# ESP-Grow_OLED_Rev_A_1.net
KiCad netlist of a schematic drawn in Altium Designer
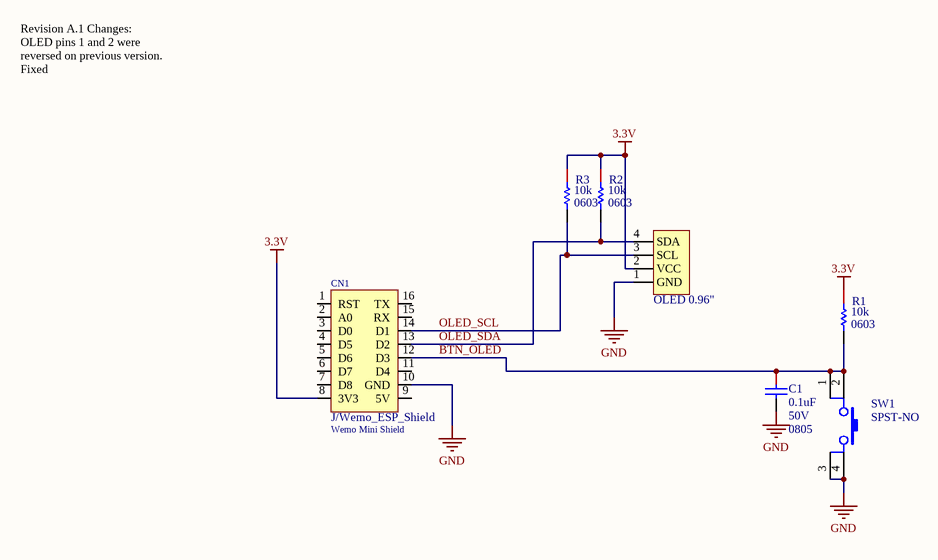
[diagram p0: ESP-Grow_OLED_Rev_A.1.SchDoc]

(export (version "E")
  (design (tool "Eeschema 10.0.6"))
  (components
    (comp (ref "C1")
      (value "0.1uF")
      (footprint "CAPC0805(2012)_L")
      (description "CAP CER 0.1UF 50V 10% X7R 0805")
      (fields
        (field (name "VOLTAGE (RATED)") "50V")
        (field (name "PACKAGE (IMPERIAL)") "0805")
        (field (name "TOLERANCE") "10%")
      )
      (libsource (lib "OLogic Nexus Vault") (part "=Capacitance"))
    )
    (comp (ref "CN1")
      (value "J/Wemo_ESP_Shield")
      (footprint "Wemos_d1_no3d")
      (description "Wemo Mini Shield for ESP-12")
      (fields (field (name "NAME") "Wemo Mini Shield"))
      (libsource (lib "Kyle_Lib_04-20-19") (part "J/Wemo_ESP_Shield"))
    )
    (comp (ref "J1")
      (value "OLED 0.96\"")
      (footprint "OLED_0.96_I2C")
      (description "SSD1306 I2C OLED 0.96\"")
      (libsource (lib "Kyle_Lib_04-20-19") (part "OLED_0.96_I2C"))
    )
    (comp (ref "R1")
      (value "10K")
      (footprint "RESC0603(1608)_M")
      (description "RES 10K OHM 1/10W 1% 0603 SMD")
      (fields
        (field (name "PACKAGE (IMPERIAL)") "0603")
        (field (name "RESISTANCE") "10k")
        (field (name "POWER") "100mW")
        (field (name "TOLERANCE") "1%")
      )
      (libsource (lib "OLogic Nexus Vault") (part "=Resistance"))
    )
    (comp (ref "R2")
      (value "10K")
      (footprint "RESC0603(1608)_M")
      (description "RES 10K OHM 1/10W 1% 0603 SMD")
      (fields
        (field (name "PACKAGE (IMPERIAL)") "0603")
        (field (name "RESISTANCE") "10k")
        (field (name "POWER") "100mW")
        (field (name "TOLERANCE") "1%")
      )
      (libsource (lib "OLogic Nexus Vault") (part "=Resistance"))
    )
    (comp (ref "R3")
      (value "10K")
      (footprint "RESC0603(1608)_M")
      (description "RES 10K OHM 1/10W 1% 0603 SMD")
      (fields
        (field (name "PACKAGE (IMPERIAL)") "0603")
        (field (name "RESISTANCE") "10k")
        (field (name "POWER") "100mW")
        (field (name "TOLERANCE") "1%")
      )
      (libsource (lib "OLogic Nexus Vault") (part "=Resistance"))
    )
    (comp (ref "SW1")
      (value "PTS645SM43SMTR92 LFS")
      (footprint "SW TACT Red 6mm x 6mm")
      (description "SWITCH TACTILE SPST-NO 0.05A 12V")
      (fields (field (name "CIRCUIT") "SPST-NO") (field (name "MANUFACTURER") "C&K"))
      (libsource (lib "altium-import") (part "root_0_PTS645SM43SMTR92 LFS_"))
    )
  )
  (nets
    (net (code "1") (name "/BTN_OLED") (class "Default")
      (node (ref "C1") (pin "1") (pinfunction "1_1") (pintype "passive"))
      (node (ref "CN1") (pin "12") (pinfunction "D3_12") (pintype "power_in"))
      (node (ref "R1") (pin "2") (pinfunction "2_2") (pintype "passive"))
      (node (ref "SW1") (pin "1") (pinfunction "1_1") (pintype "passive"))
      (node (ref "SW1") (pin "2") (pinfunction "2_2") (pintype "passive"))
    )
    (net (code "2") (name "/OLED_SCL") (class "Default")
      (node (ref "CN1") (pin "14") (pinfunction "D1_14") (pintype "power_in"))
      (node (ref "J1") (pin "3") (pinfunction "SCL_3") (pintype "passive"))
      (node (ref "R3") (pin "2") (pinfunction "2_2") (pintype "passive"))
    )
    (net (code "3") (name "/OLED_SDA") (class "Default")
      (node (ref "CN1") (pin "13") (pinfunction "D2_13") (pintype "power_in"))
      (node (ref "J1") (pin "4") (pinfunction "SDA_4") (pintype "passive"))
      (node (ref "R2") (pin "2") (pinfunction "2_2") (pintype "passive"))
    )
    (net (code "4") (name "3.3V") (class "Default")
      (node (ref "CN1") (pin "8") (pinfunction "3V3_8") (pintype "power_in"))
      (node (ref "J1") (pin "2") (pinfunction "VCC_2") (pintype "passive"))
      (node (ref "R1") (pin "1") (pinfunction "1_1") (pintype "passive"))
      (node (ref "R2") (pin "1") (pinfunction "1_1") (pintype "passive"))
      (node (ref "R3") (pin "1") (pinfunction "1_1") (pintype "passive"))
    )
    (net (code "5") (name "GND") (class "Default")
      (node (ref "C1") (pin "2") (pinfunction "2_2") (pintype "passive"))
      (node (ref "CN1") (pin "10") (pinfunction "GND_10") (pintype "power_in"))
      (node (ref "J1") (pin "1") (pinfunction "GND_1") (pintype "passive"))
      (node (ref "SW1") (pin "3") (pinfunction "3_3") (pintype "passive"))
      (node (ref "SW1") (pin "4") (pinfunction "4_4") (pintype "passive"))
    )
    (net (code "6") (name "unconnected-(CN1-5V-Pad9)") (class "Default")
      (node (ref "CN1") (pin "9") (pinfunction "5V_9") (pintype "power_in"))
    )
    (net (code "7") (name "unconnected-(CN1-A0-Pad2)") (class "Default")
      (node (ref "CN1") (pin "2") (pinfunction "A0_2") (pintype "power_in"))
    )
    (net (code "8") (name "unconnected-(CN1-D0-Pad3)") (class "Default")
      (node (ref "CN1") (pin "3") (pinfunction "D0_3") (pintype "power_in"))
    )
    (net (code "9") (name "unconnected-(CN1-D4-Pad11)") (class "Default")
      (node (ref "CN1") (pin "11") (pinfunction "D4_11") (pintype "power_in"))
    )
    (net (code "10") (name "unconnected-(CN1-D5-Pad4)") (class "Default")
      (node (ref "CN1") (pin "4") (pinfunction "D5_4") (pintype "power_in"))
    )
    (net (code "11") (name "unconnected-(CN1-D6-Pad5)") (class "Default")
      (node (ref "CN1") (pin "5") (pinfunction "D6_5") (pintype "power_in"))
    )
    (net (code "12") (name "unconnected-(CN1-D7-Pad6)") (class "Default")
      (node (ref "CN1") (pin "6") (pinfunction "D7_6") (pintype "power_in"))
    )
    (net (code "13") (name "unconnected-(CN1-D8-Pad7)") (class "Default")
      (node (ref "CN1") (pin "7") (pinfunction "D8_7") (pintype "power_in"))
    )
    (net (code "14") (name "unconnected-(CN1-RST-Pad1)") (class "Default")
      (node (ref "CN1") (pin "1") (pinfunction "RST_1") (pintype "power_in"))
    )
    (net (code "15") (name "unconnected-(CN1-RX-Pad15)") (class "Default")
      (node (ref "CN1") (pin "15") (pinfunction "RX_15") (pintype "power_in"))
    )
    (net (code "16") (name "unconnected-(CN1-TX-Pad16)") (class "Default")
      (node (ref "CN1") (pin "16") (pinfunction "TX_16") (pintype "power_in"))
    )
  )
)
